# TPS61169_HPLED.net
KiCad netlist of a schematic drawn in EAGLE
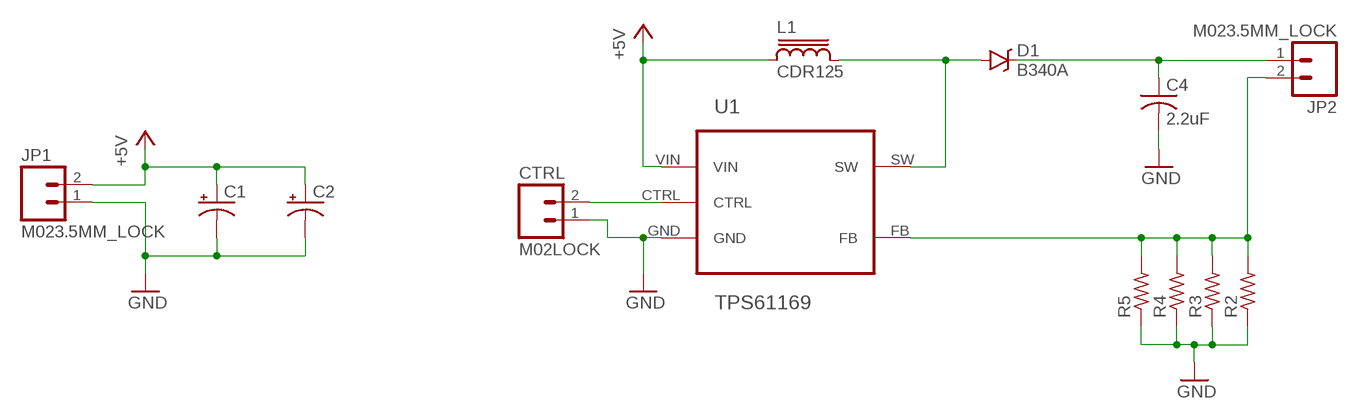
[diagram p0: schematic, sheet 1]

(export (version "E")
  (design (tool "Eeschema 10.0.6"))
  (components
    (comp (ref "C1")
      (value "CPOL-USE3.5-8")
      (footprint "eagle-import:E3,5-8")
      (libsource (lib "eagle-import") (part "CPOL-USE3.5-8"))
    )
    (comp (ref "C2")
      (value "CPOL-USE3.5-8")
      (footprint "eagle-import:E3,5-8")
      (libsource (lib "eagle-import") (part "CPOL-USE3.5-8"))
    )
    (comp (ref "C4")
      (value "2.2uF")
      (footprint "eagle-import:C0805")
      (libsource (lib "eagle-import") (part "C-USC0805"))
    )
    (comp (ref "CTRL")
      (value "M02LOCK")
      (footprint "eagle-import:1X02_LOCK")
      (libsource (lib "eagle-import") (part "M02LOCK"))
    )
    (comp (ref "D1")
      (value "B340A")
      (footprint "eagle-import:SMA-DIODE")
      (libsource (lib "eagle-import") (part "DIODE-SCHOTTKY-B340A"))
    )
    (comp (ref "JP1")
      (value "M023.5MM_LOCK")
      (footprint "eagle-import:SCREWTERMINAL-3.5MM-2_LOCK")
      (libsource (lib "eagle-import") (part "M023.5MM_LOCK"))
    )
    (comp (ref "JP2")
      (value "M023.5MM_LOCK")
      (footprint "eagle-import:SCREWTERMINAL-3.5MM-2_LOCK")
      (libsource (lib "eagle-import") (part "M023.5MM_LOCK"))
    )
    (comp (ref "L1")
      (value "CDR125")
      (footprint "eagle-import:CDR125")
      (libsource (lib "eagle-import") (part "CDR125"))
    )
    (comp (ref "R2")
      (value "R-US_R0805")
      (footprint "eagle-import:R0805")
      (libsource (lib "eagle-import") (part "R-US_R0805"))
    )
    (comp (ref "R3")
      (value "R-US_R0805")
      (footprint "eagle-import:R0805")
      (libsource (lib "eagle-import") (part "R-US_R0805"))
    )
    (comp (ref "R4")
      (value "R-US_R0805")
      (footprint "eagle-import:R0805")
      (libsource (lib "eagle-import") (part "R-US_R0805"))
    )
    (comp (ref "R5")
      (value "R-US_R0805")
      (footprint "eagle-import:R0805")
      (libsource (lib "eagle-import") (part "R-US_R0805"))
    )
    (comp (ref "U1")
      (value "TPS61169")
      (footprint "eagle-import:SOT65P210X110-5N")
      (fields (field (name "MPN") "74AHCT1G04GW/T1"))
      (libsource (lib "eagle-import") (part "74AHCT1G04GW/T1"))
    )
  )
  (nets
    (net (code "1") (name "+5V") (class "Default")
      (node (ref "C1") (pin "+") (pinfunction "+_+") (pintype "passive"))
      (node (ref "C2") (pin "+") (pinfunction "+_+") (pintype "passive"))
      (node (ref "JP1") (pin "2") (pinfunction "2_2") (pintype "passive"))
      (node (ref "L1") (pin "1") (pinfunction "1_1") (pintype "passive"))
      (node (ref "U1") (pin "VIN") (pinfunction "VIN_VIN") (pintype "power_in"))
    )
    (net (code "2") (name "GND") (class "Default")
      (node (ref "C1") (pin "-") (pinfunction "-_-") (pintype "passive"))
      (node (ref "C2") (pin "-") (pinfunction "-_-") (pintype "passive"))
      (node (ref "C4") (pin "2") (pinfunction "2_2") (pintype "passive"))
      (node (ref "CTRL") (pin "1") (pinfunction "1_1") (pintype "passive"))
      (node (ref "JP1") (pin "1") (pinfunction "1_1") (pintype "passive"))
      (node (ref "R2") (pin "1") (pinfunction "1_1") (pintype "passive"))
      (node (ref "R3") (pin "1") (pinfunction "1_1") (pintype "passive"))
      (node (ref "R4") (pin "1") (pinfunction "1_1") (pintype "passive"))
      (node (ref "R5") (pin "1") (pinfunction "1_1") (pintype "passive"))
      (node (ref "U1") (pin "GND") (pinfunction "GND_GND") (pintype "power_in"))
    )
    (net (code "3") (name "Net-(C4-Pad1)") (class "Default")
      (node (ref "C4") (pin "1") (pinfunction "1_1") (pintype "passive"))
      (node (ref "D1") (pin "C") (pinfunction "C_C") (pintype "passive"))
      (node (ref "JP2") (pin "1") (pinfunction "1_1") (pintype "passive"))
    )
    (net (code "4") (name "Net-(CTRL-Pad2)") (class "Default")
      (node (ref "CTRL") (pin "2") (pinfunction "2_2") (pintype "passive"))
      (node (ref "U1") (pin "CTRL") (pinfunction "CTRL_CTRL") (pintype "input"))
    )
    (net (code "5") (name "Net-(D1-PadA)") (class "Default")
      (node (ref "D1") (pin "A") (pinfunction "A_A") (pintype "passive"))
      (node (ref "L1") (pin "2") (pinfunction "2_2") (pintype "passive"))
      (node (ref "U1") (pin "SW") (pinfunction "SW_SW") (pintype "output"))
    )
    (net (code "6") (name "Net-(JP2-Pad2)") (class "Default")
      (node (ref "JP2") (pin "2") (pinfunction "2_2") (pintype "passive"))
      (node (ref "R2") (pin "2") (pinfunction "2_2") (pintype "passive"))
      (node (ref "R3") (pin "2") (pinfunction "2_2") (pintype "passive"))
      (node (ref "R4") (pin "2") (pinfunction "2_2") (pintype "passive"))
      (node (ref "R5") (pin "2") (pinfunction "2_2") (pintype "passive"))
      (node (ref "U1") (pin "FB") (pinfunction "FB_FB") (pintype "input"))
    )
  )
)
